# mapleCUx_large_047.net
KiCad netlist of a schematic drawn in EAGLE
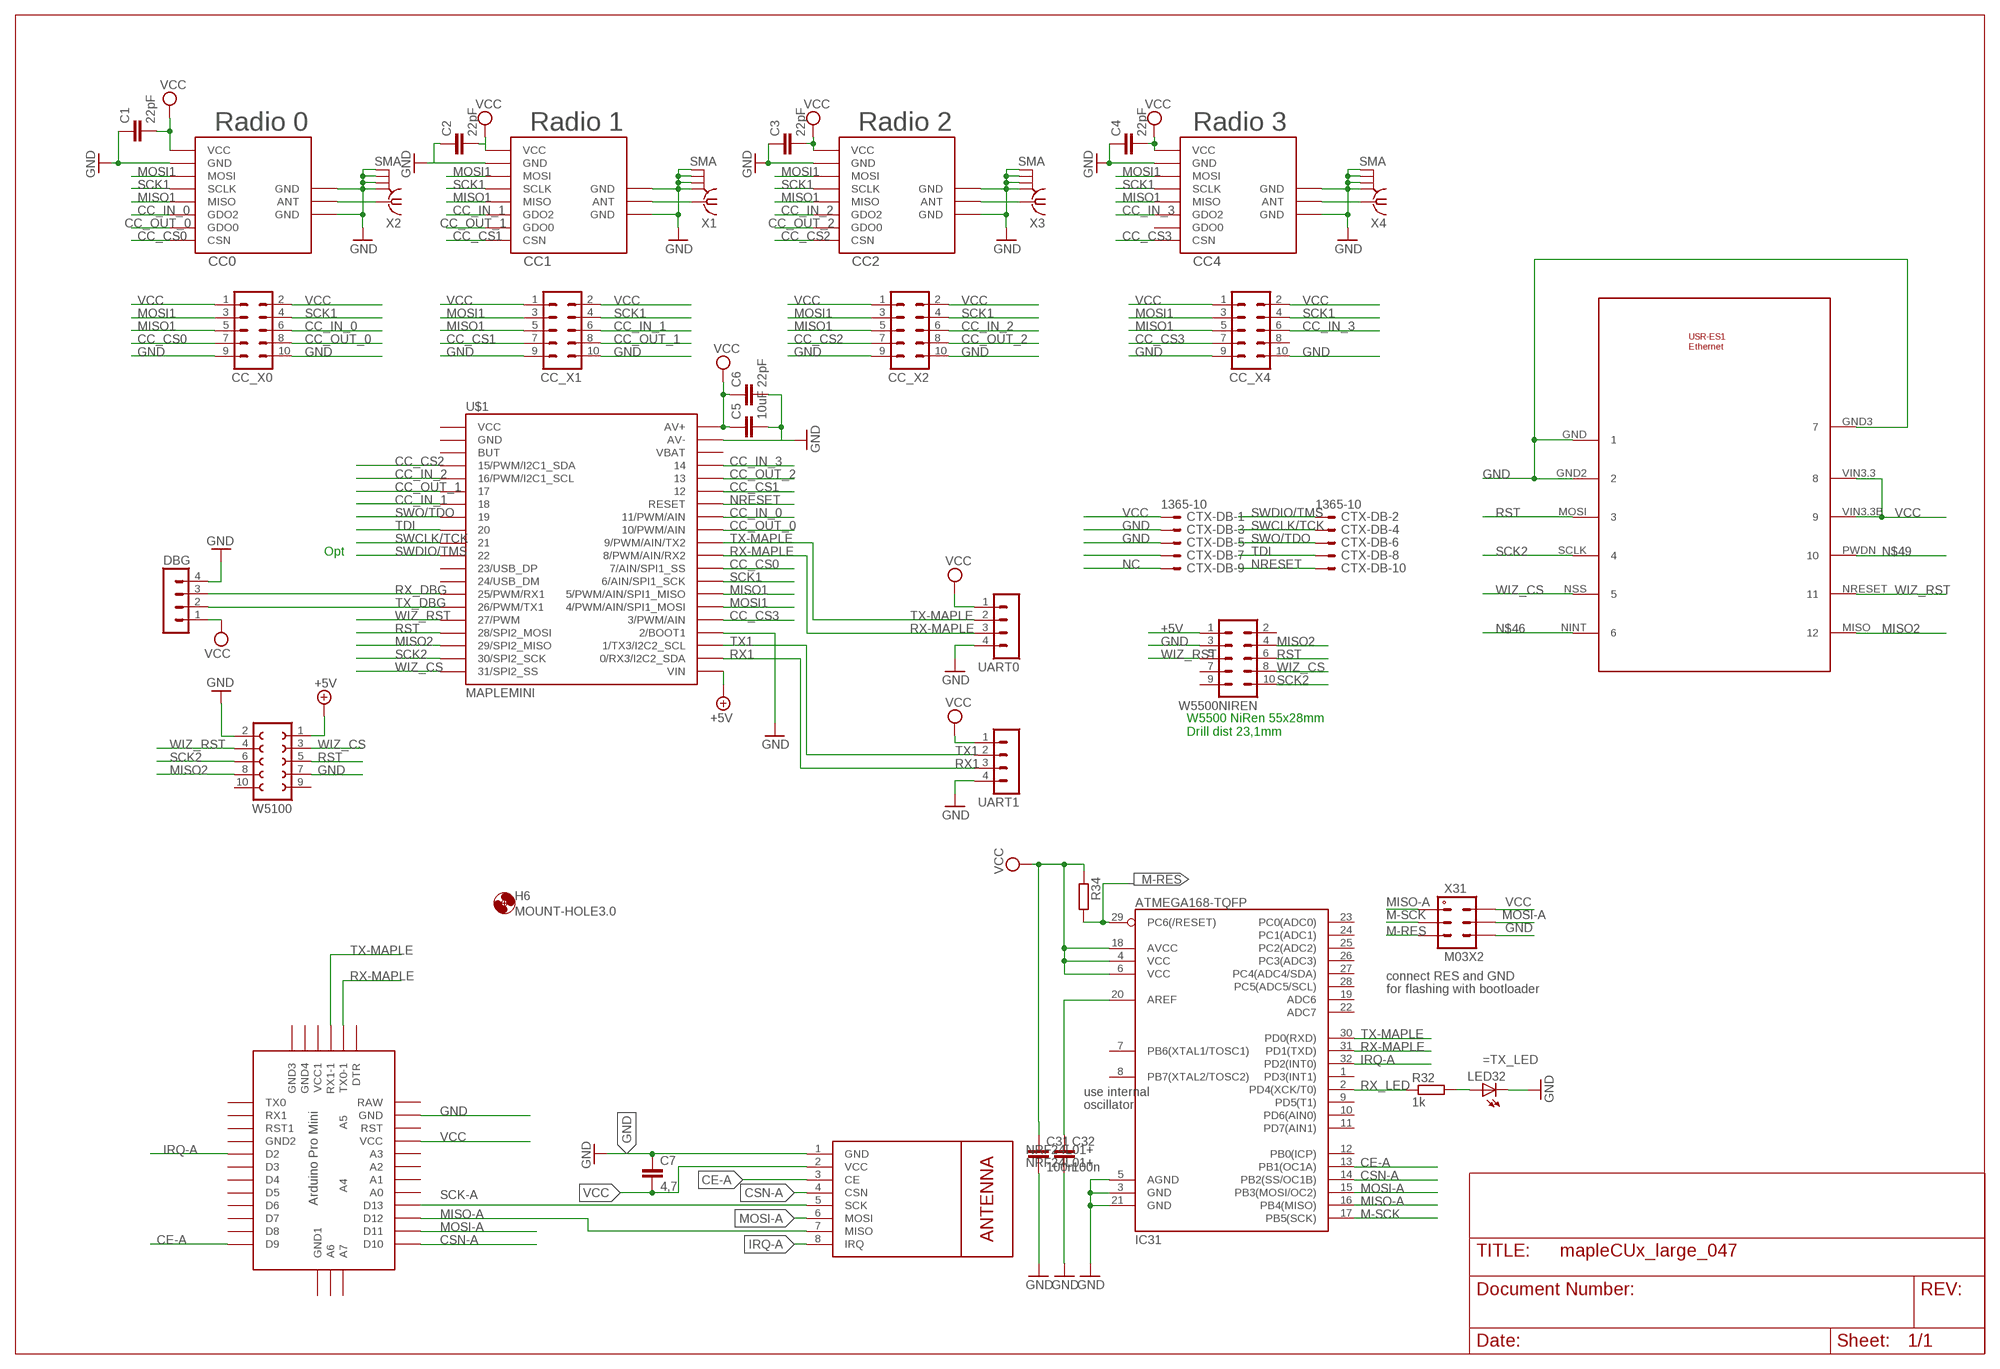
[diagram p0: schematic, sheet 1]

(export (version "E")
  (design (tool "Eeschema 10.0.6"))
  (components
    (comp (ref "C1")
      (value "22pF")
      (footprint "eagle-import:C0805")
      (libsource (lib "eagle-import") (part "C-EUC0805"))
    )
    (comp (ref "C2")
      (value "22pF")
      (footprint "eagle-import:C0805")
      (libsource (lib "eagle-import") (part "C-EUC0805"))
    )
    (comp (ref "C3")
      (value "22pF")
      (footprint "eagle-import:C0805")
      (libsource (lib "eagle-import") (part "C-EUC0805"))
    )
    (comp (ref "C4")
      (value "22pF")
      (footprint "eagle-import:C0805")
      (libsource (lib "eagle-import") (part "C-EUC0805"))
    )
    (comp (ref "C5")
      (value "10uF")
      (footprint "eagle-import:C1210")
      (libsource (lib "eagle-import") (part "C-EUC1210"))
    )
    (comp (ref "C6")
      (value "22pF")
      (footprint "eagle-import:C0805")
      (libsource (lib "eagle-import") (part "C-EUC0805"))
    )
    (comp (ref "C7")
      (value "4,7")
      (footprint "eagle-import:C1210")
      (libsource (lib "eagle-import") (part "C-EUC1210"))
    )
    (comp (ref "C31")
      (value "100n")
      (footprint "eagle-import:C0805")
      (libsource (lib "eagle-import") (part "C-EUC0805"))
    )
    (comp (ref "C32")
      (value "100n")
      (footprint "eagle-import:C0805")
      (libsource (lib "eagle-import") (part "C-EUC0805"))
    )
    (comp (ref "CC0")
      (value "CC1101_MODULE1SMD")
      (footprint "eagle-import:CC1101_MODULE1_SMD")
      (libsource (lib "eagle-import") (part "CC1101_MODULE1SMD"))
    )
    (comp (ref "CC1")
      (value "CC1101_MODULE1SMD")
      (footprint "eagle-import:CC1101_MODULE1_SMD")
      (libsource (lib "eagle-import") (part "CC1101_MODULE1SMD"))
    )
    (comp (ref "CC2")
      (value "CC1101_MODULE1SMD")
      (footprint "eagle-import:CC1101_MODULE1_SMD")
      (libsource (lib "eagle-import") (part "CC1101_MODULE1SMD"))
    )
    (comp (ref "CC4")
      (value "CC1101_MODULE1SMD")
      (footprint "eagle-import:CC1101_MODULE1_SMD")
      (libsource (lib "eagle-import") (part "CC1101_MODULE1SMD"))
    )
    (comp (ref "CC_X0")
      (value "MA05-2")
      (footprint "eagle-import:MA05-2")
      (libsource (lib "eagle-import") (part "MA05-2"))
    )
    (comp (ref "CC_X1")
      (value "MA05-2")
      (footprint "eagle-import:MA05-2")
      (libsource (lib "eagle-import") (part "MA05-2"))
    )
    (comp (ref "CC_X2")
      (value "MA05-2")
      (footprint "eagle-import:MA05-2")
      (libsource (lib "eagle-import") (part "MA05-2"))
    )
    (comp (ref "CC_X4")
      (value "MA05-2")
      (footprint "eagle-import:MA05-2")
      (libsource (lib "eagle-import") (part "MA05-2"))
    )
    (comp (ref "CTX-DB")
      (value "1365-10")
      (footprint "eagle-import:1365-10")
      (libsource (lib "eagle-import") (part "1365-10"))
    )
    (comp (ref "DBG")
      (value "MA04-1")
      (footprint "eagle-import:MA04-1")
      (libsource (lib "eagle-import") (part "MA04-1"))
    )
    (comp (ref "H6")
      (value "MOUNT-HOLE3.0")
      (footprint "eagle-import:3,0")
      (libsource (lib "eagle-import") (part "MOUNT-HOLE3.0"))
    )
    (comp (ref "IC31")
      (value "ATMEGA168-TQFP")
      (footprint "eagle-import:TQFP32-08")
      (libsource (lib "eagle-import") (part "ATMEGA168-TQFP"))
    )
    (comp (ref "LED32")
      (value "LEDCHIPLED_0805")
      (footprint "eagle-import:CHIPLED_0805")
      (libsource (lib "eagle-import") (part "LEDCHIPLED_0805"))
    )
    (comp (ref "NRF24L01+")
      (value "NRF24L01+")
      (footprint "eagle-import:WIRELESS-NRF24L01")
      (libsource (lib "eagle-import") (part "WIRELESS-NRF24L01"))
    )
    (comp (ref "R32")
      (value "1k")
      (footprint "eagle-import:R0805")
      (libsource (lib "eagle-import") (part "R-EU_R0805"))
    )
    (comp (ref "R34")
      (value "R-EU_R0805")
      (footprint "eagle-import:R0805")
      (libsource (lib "eagle-import") (part "R-EU_R0805"))
    )
    (comp (ref "U$1")
      (value "MAPLEMINI")
      (footprint "eagle-import:20-DIP")
      (libsource (lib "eagle-import") (part "MAPLEMINI"))
    )
    (comp (ref "U$2")
      (value "ABK-PRO-MINI")
      (footprint "eagle-import:ABK-PRO-MINI")
      (libsource (lib "eagle-import") (part "ABK-PRO-MINI"))
    )
    (comp (ref "U$3")
      (value "USR-ES1")
      (footprint "eagle-import:USR-ES1")
      (libsource (lib "eagle-import") (part "USR-ES1"))
    )
    (comp (ref "UART0")
      (value "MA04-1")
      (footprint "eagle-import:MA04-1")
      (libsource (lib "eagle-import") (part "MA04-1"))
    )
    (comp (ref "UART1")
      (value "MA04-1")
      (footprint "eagle-import:MA04-1")
      (libsource (lib "eagle-import") (part "MA04-1"))
    )
    (comp (ref "W5100")
      (value "FE05-2")
      (footprint "eagle-import:FE05-2")
      (libsource (lib "eagle-import") (part "FE05-2"))
    )
    (comp (ref "W5500NIREN")
      (value "MA05-2")
      (footprint "eagle-import:MA05-2")
      (libsource (lib "eagle-import") (part "MA05-2"))
    )
    (comp (ref "X1")
      (value "SMA")
      (footprint "eagle-import:SMA")
      (libsource (lib "eagle-import") (part "SMA"))
    )
    (comp (ref "X2")
      (value "SMA")
      (footprint "eagle-import:SMA")
      (libsource (lib "eagle-import") (part "SMA"))
    )
    (comp (ref "X3")
      (value "SMA")
      (footprint "eagle-import:SMA")
      (libsource (lib "eagle-import") (part "SMA"))
    )
    (comp (ref "X4")
      (value "SMA")
      (footprint "eagle-import:SMA")
      (libsource (lib "eagle-import") (part "SMA"))
    )
    (comp (ref "X31")
      (value "M03X2")
      (footprint "eagle-import:2X03-1.27MM_SMD")
      (libsource (lib "eagle-import") (part "M03X2"))
    )
  )
  (nets
    (net (code "1") (name "+5V") (class "Default")
      (node (ref "U$1") (pin "21") (pinfunction "VIN_21") (pintype "bidirectional"))
      (node (ref "W5100") (pin "1") (pinfunction "1_1") (pintype "passive"))
      (node (ref "W5500NIREN") (pin "1") (pinfunction "1_1") (pintype "passive"))
    )
    (net (code "2") (name "/CC_CS0") (class "Default")
      (node (ref "CC0") (pin "CSN") (pinfunction "CSN_CSN") (pintype "bidirectional"))
      (node (ref "CC_X0") (pin "7") (pinfunction "7_7") (pintype "passive"))
      (node (ref "U$1") (pin "29") (pinfunction "7/AIN/SPI1_SS_29") (pintype "bidirectional"))
    )
    (net (code "3") (name "/CC_CS1") (class "Default")
      (node (ref "CC1") (pin "CSN") (pinfunction "CSN_CSN") (pintype "bidirectional"))
      (node (ref "CC_X1") (pin "7") (pinfunction "7_7") (pintype "passive"))
      (node (ref "U$1") (pin "35") (pinfunction "12_35") (pintype "bidirectional"))
    )
    (net (code "4") (name "/CC_CS2") (class "Default")
      (node (ref "CC2") (pin "CSN") (pinfunction "CSN_CSN") (pintype "bidirectional"))
      (node (ref "CC_X2") (pin "7") (pinfunction "7_7") (pintype "passive"))
      (node (ref "U$1") (pin "4") (pinfunction "15/PWM/I2C1_SDA_4") (pintype "bidirectional"))
    )
    (net (code "5") (name "/CC_CS3") (class "Default")
      (node (ref "CC4") (pin "CSN") (pinfunction "CSN_CSN") (pintype "bidirectional"))
      (node (ref "CC_X4") (pin "7") (pinfunction "7_7") (pintype "passive"))
      (node (ref "U$1") (pin "25") (pinfunction "3/PWM/AIN_25") (pintype "bidirectional"))
    )
    (net (code "6") (name "/CC_IN_0") (class "Default")
      (node (ref "CC0") (pin "GDO2") (pinfunction "GDO2_GDO2") (pintype "bidirectional"))
      (node (ref "CC_X0") (pin "6") (pinfunction "6_6") (pintype "passive"))
      (node (ref "U$1") (pin "33") (pinfunction "11/PWM/AIN_33") (pintype "bidirectional"))
    )
    (net (code "7") (name "/CC_IN_1") (class "Default")
      (node (ref "CC1") (pin "GDO2") (pinfunction "GDO2_GDO2") (pintype "bidirectional"))
      (node (ref "CC_X1") (pin "6") (pinfunction "6_6") (pintype "passive"))
      (node (ref "U$1") (pin "7") (pinfunction "18_7") (pintype "bidirectional"))
    )
    (net (code "8") (name "/CC_IN_2") (class "Default")
      (node (ref "CC2") (pin "GDO2") (pinfunction "GDO2_GDO2") (pintype "bidirectional"))
      (node (ref "CC_X2") (pin "6") (pinfunction "6_6") (pintype "passive"))
      (node (ref "U$1") (pin "5") (pinfunction "16/PWM/I2C1_SCL_5") (pintype "bidirectional"))
    )
    (net (code "9") (name "/CC_IN_3") (class "Default")
      (node (ref "CC4") (pin "GDO2") (pinfunction "GDO2_GDO2") (pintype "bidirectional"))
      (node (ref "CC_X4") (pin "6") (pinfunction "6_6") (pintype "passive"))
      (node (ref "U$1") (pin "37") (pinfunction "14_37") (pintype "bidirectional"))
    )
    (net (code "10") (name "/CC_OUT_0") (class "Default")
      (node (ref "CC0") (pin "GDO0") (pinfunction "GDO0_GDO0") (pintype "bidirectional"))
      (node (ref "CC_X0") (pin "8") (pinfunction "8_8") (pintype "passive"))
      (node (ref "U$1") (pin "32") (pinfunction "10/PWM/AIN_32") (pintype "bidirectional"))
    )
    (net (code "11") (name "/CC_OUT_1") (class "Default")
      (node (ref "CC1") (pin "GDO0") (pinfunction "GDO0_GDO0") (pintype "bidirectional"))
      (node (ref "CC_X1") (pin "8") (pinfunction "8_8") (pintype "passive"))
      (node (ref "U$1") (pin "6") (pinfunction "17_6") (pintype "bidirectional"))
    )
    (net (code "12") (name "/CC_OUT_2") (class "Default")
      (node (ref "CC2") (pin "GDO0") (pinfunction "GDO0_GDO0") (pintype "bidirectional"))
      (node (ref "CC_X2") (pin "8") (pinfunction "8_8") (pintype "passive"))
      (node (ref "U$1") (pin "36") (pinfunction "13_36") (pintype "bidirectional"))
    )
    (net (code "13") (name "/M-RES") (class "Default")
      (node (ref "IC31") (pin "29") (pinfunction "PC6(/RESET)_29") (pintype "bidirectional"))
      (node (ref "R34") (pin "2") (pinfunction "2_2") (pintype "passive"))
      (node (ref "X31") (pin "P$5") (pinfunction "5_P$5") (pintype "passive"))
    )
    (net (code "14") (name "/M-SCK") (class "Default")
      (node (ref "IC31") (pin "17") (pinfunction "PB5(SCK)_17") (pintype "bidirectional"))
      (node (ref "X31") (pin "P$3") (pinfunction "3_P$3") (pintype "passive"))
    )
    (net (code "15") (name "/MISO-A") (class "Default")
      (node (ref "IC31") (pin "16") (pinfunction "PB4(MISO)_16") (pintype "bidirectional"))
      (node (ref "NRF24L01+") (pin "7") (pinfunction "MISO_7") (pintype "bidirectional"))
      (node (ref "U$2") (pin "D12") (pinfunction "D12_D12") (pintype "bidirectional"))
      (node (ref "X31") (pin "P$1") (pinfunction "1_P$1") (pintype "passive"))
    )
    (net (code "16") (name "/MISO1") (class "Default")
      (node (ref "CC0") (pin "MISO") (pinfunction "MISO_MISO") (pintype "bidirectional"))
      (node (ref "CC1") (pin "MISO") (pinfunction "MISO_MISO") (pintype "bidirectional"))
      (node (ref "CC2") (pin "MISO") (pinfunction "MISO_MISO") (pintype "bidirectional"))
      (node (ref "CC4") (pin "MISO") (pinfunction "MISO_MISO") (pintype "bidirectional"))
      (node (ref "CC_X0") (pin "5") (pinfunction "5_5") (pintype "passive"))
      (node (ref "CC_X1") (pin "5") (pinfunction "5_5") (pintype "passive"))
      (node (ref "CC_X2") (pin "5") (pinfunction "5_5") (pintype "passive"))
      (node (ref "CC_X4") (pin "5") (pinfunction "5_5") (pintype "passive"))
      (node (ref "U$1") (pin "27") (pinfunction "5/PWM/AIN/SPI1_MISO_27") (pintype "bidirectional"))
    )
    (net (code "17") (name "/MISO2") (class "Default")
      (node (ref "U$1") (pin "18") (pinfunction "29/SPI2_MISO_18") (pintype "bidirectional"))
      (node (ref "U$3") (pin "MISO") (pinfunction "12_MISO") (pintype "bidirectional"))
      (node (ref "W5100") (pin "8") (pinfunction "8_8") (pintype "passive"))
      (node (ref "W5500NIREN") (pin "4") (pinfunction "4_4") (pintype "passive"))
    )
    (net (code "18") (name "/MOSI1") (class "Default")
      (node (ref "CC0") (pin "MOSI") (pinfunction "MOSI_MOSI") (pintype "bidirectional"))
      (node (ref "CC1") (pin "MOSI") (pinfunction "MOSI_MOSI") (pintype "bidirectional"))
      (node (ref "CC2") (pin "MOSI") (pinfunction "MOSI_MOSI") (pintype "bidirectional"))
      (node (ref "CC4") (pin "MOSI") (pinfunction "MOSI_MOSI") (pintype "bidirectional"))
      (node (ref "CC_X0") (pin "3") (pinfunction "3_3") (pintype "passive"))
      (node (ref "CC_X1") (pin "3") (pinfunction "3_3") (pintype "passive"))
      (node (ref "CC_X2") (pin "3") (pinfunction "3_3") (pintype "passive"))
      (node (ref "CC_X4") (pin "3") (pinfunction "3_3") (pintype "passive"))
      (node (ref "U$1") (pin "26") (pinfunction "4/PWM/AIN/SPI1_MOSI_26") (pintype "bidirectional"))
    )
    (net (code "19") (name "/N$46") (class "Default")
      (node (ref "U$3") (pin "NINT") (pinfunction "6_NINT") (pintype "bidirectional"))
    )
    (net (code "20") (name "/N$49") (class "Default")
      (node (ref "U$3") (pin "PWDN") (pinfunction "10_PWDN") (pintype "bidirectional"))
    )
    (net (code "21") (name "/NC") (class "Default")
      (node (ref "CTX-DB") (pin "9") (pinfunction "S_9") (pintype "passive"))
    )
    (net (code "22") (name "/NRESET") (class "Default")
      (node (ref "CTX-DB") (pin "10") (pinfunction "S_10") (pintype "passive"))
      (node (ref "U$1") (pin "34") (pinfunction "RESET_34") (pintype "bidirectional"))
    )
    (net (code "23") (name "/RST") (class "Default")
      (node (ref "U$1") (pin "17") (pinfunction "28/SPI2_MOSI_17") (pintype "bidirectional"))
      (node (ref "U$3") (pin "MOSI") (pinfunction "3_MOSI") (pintype "bidirectional"))
      (node (ref "W5100") (pin "5") (pinfunction "5_5") (pintype "passive"))
      (node (ref "W5500NIREN") (pin "6") (pinfunction "6_6") (pintype "passive"))
    )
    (net (code "24") (name "/RX-MAPLE") (class "Default")
      (node (ref "IC31") (pin "31") (pinfunction "PD1(TXD)_31") (pintype "bidirectional"))
      (node (ref "U$1") (pin "30") (pinfunction "8/PWM/AIN/RX2_30") (pintype "bidirectional"))
      (node (ref "U$2") (pin "TX0-1") (pinfunction "TX0-1_TX0-1") (pintype "bidirectional"))
      (node (ref "UART0") (pin "3") (pinfunction "3_3") (pintype "passive"))
    )
    (net (code "25") (name "/RX1") (class "Default")
      (node (ref "U$1") (pin "22") (pinfunction "0/RX3/I2C2_SDA_22") (pintype "bidirectional"))
      (node (ref "UART1") (pin "3") (pinfunction "3_3") (pintype "passive"))
    )
    (net (code "26") (name "/RX_DBG") (class "Default")
      (node (ref "DBG") (pin "3") (pinfunction "3_3") (pintype "passive"))
      (node (ref "U$1") (pin "14") (pinfunction "25/PWM/RX1_14") (pintype "bidirectional"))
    )
    (net (code "27") (name "/RX_LED") (class "Default")
      (node (ref "IC31") (pin "2") (pinfunction "PD4(XCK/T0)_2") (pintype "bidirectional"))
      (node (ref "R32") (pin "1") (pinfunction "1_1") (pintype "passive"))
    )
    (net (code "28") (name "/SCK-A") (class "Default")
      (node (ref "NRF24L01+") (pin "5") (pinfunction "SCK_5") (pintype "bidirectional"))
      (node (ref "U$2") (pin "D13") (pinfunction "D13_D13") (pintype "bidirectional"))
    )
    (net (code "29") (name "/SCK1") (class "Default")
      (node (ref "CC0") (pin "SCLK") (pinfunction "SCLK_SCLK") (pintype "bidirectional"))
      (node (ref "CC1") (pin "SCLK") (pinfunction "SCLK_SCLK") (pintype "bidirectional"))
      (node (ref "CC2") (pin "SCLK") (pinfunction "SCLK_SCLK") (pintype "bidirectional"))
      (node (ref "CC4") (pin "SCLK") (pinfunction "SCLK_SCLK") (pintype "bidirectional"))
      (node (ref "CC_X0") (pin "4") (pinfunction "4_4") (pintype "passive"))
      (node (ref "CC_X1") (pin "4") (pinfunction "4_4") (pintype "passive"))
      (node (ref "CC_X2") (pin "4") (pinfunction "4_4") (pintype "passive"))
      (node (ref "CC_X4") (pin "4") (pinfunction "4_4") (pintype "passive"))
      (node (ref "U$1") (pin "28") (pinfunction "6/AIN/SPI1_SCK_28") (pintype "bidirectional"))
    )
    (net (code "30") (name "/SCK2") (class "Default")
      (node (ref "U$1") (pin "19") (pinfunction "30/SPI2_SCK_19") (pintype "bidirectional"))
      (node (ref "U$3") (pin "SCLK") (pinfunction "4_SCLK") (pintype "bidirectional"))
      (node (ref "W5100") (pin "6") (pinfunction "6_6") (pintype "passive"))
      (node (ref "W5500NIREN") (pin "10") (pinfunction "10_10") (pintype "passive"))
    )
    (net (code "31") (name "/SWCLK{slash}TCK") (class "Default")
      (node (ref "CTX-DB") (pin "4") (pinfunction "S_4") (pintype "passive"))
      (node (ref "U$1") (pin "10") (pinfunction "21_10") (pintype "bidirectional"))
    )
    (net (code "32") (name "/SWDIO{slash}TMS") (class "Default")
      (node (ref "CTX-DB") (pin "2") (pinfunction "S_2") (pintype "passive"))
      (node (ref "U$1") (pin "11") (pinfunction "22_11") (pintype "bidirectional"))
    )
    (net (code "33") (name "/SWO{slash}TDO") (class "Default")
      (node (ref "CTX-DB") (pin "6") (pinfunction "S_6") (pintype "passive"))
      (node (ref "U$1") (pin "8") (pinfunction "19_8") (pintype "bidirectional"))
    )
    (net (code "34") (name "/TDI") (class "Default")
      (node (ref "CTX-DB") (pin "8") (pinfunction "S_8") (pintype "passive"))
      (node (ref "U$1") (pin "9") (pinfunction "20_9") (pintype "bidirectional"))
    )
    (net (code "35") (name "/TX-MAPLE") (class "Default")
      (node (ref "IC31") (pin "30") (pinfunction "PD0(RXD)_30") (pintype "bidirectional"))
      (node (ref "U$1") (pin "31") (pinfunction "9/PWM/AIN/TX2_31") (pintype "bidirectional"))
      (node (ref "U$2") (pin "RX1-1") (pinfunction "RX1-1_RX1-1") (pintype "bidirectional"))
      (node (ref "UART0") (pin "2") (pinfunction "2_2") (pintype "passive"))
    )
    (net (code "36") (name "/TX1") (class "Default")
      (node (ref "U$1") (pin "23") (pinfunction "1/TX3/I2C2_SCL_23") (pintype "bidirectional"))
      (node (ref "UART1") (pin "2") (pinfunction "2_2") (pintype "passive"))
    )
    (net (code "37") (name "/TX_DBG") (class "Default")
      (node (ref "DBG") (pin "2") (pinfunction "2_2") (pintype "passive"))
      (node (ref "U$1") (pin "15") (pinfunction "26/PWM/TX1_15") (pintype "bidirectional"))
    )
    (net (code "38") (name "/WIZ_CS") (class "Default")
      (node (ref "U$1") (pin "20") (pinfunction "31/SPI2_SS_20") (pintype "bidirectional"))
      (node (ref "U$3") (pin "NSS") (pinfunction "5_NSS") (pintype "bidirectional"))
      (node (ref "W5100") (pin "3") (pinfunction "3_3") (pintype "passive"))
      (node (ref "W5500NIREN") (pin "8") (pinfunction "8_8") (pintype "passive"))
    )
    (net (code "39") (name "/WIZ_RST") (class "Default")
      (node (ref "U$1") (pin "16") (pinfunction "27/PWM_16") (pintype "bidirectional"))
      (node (ref "U$3") (pin "NRESET") (pinfunction "11_NRESET") (pintype "bidirectional"))
      (node (ref "W5100") (pin "4") (pinfunction "4_4") (pintype "passive"))
      (node (ref "W5500NIREN") (pin "5") (pinfunction "5_5") (pintype "passive"))
    )
    (net (code "40") (name "CE-A") (class "Default")
      (node (ref "IC31") (pin "13") (pinfunction "PB1(OC1A)_13") (pintype "bidirectional"))
      (node (ref "NRF24L01+") (pin "3") (pinfunction "CE_3") (pintype "bidirectional"))
      (node (ref "U$2") (pin "D9") (pinfunction "D9_D9") (pintype "bidirectional"))
    )
    (net (code "41") (name "CSN-A") (class "Default")
      (node (ref "IC31") (pin "14") (pinfunction "PB2(SS/OC1B)_14") (pintype "bidirectional"))
      (node (ref "NRF24L01+") (pin "4") (pinfunction "CSN_4") (pintype "bidirectional"))
      (node (ref "U$2") (pin "D10") (pinfunction "D10_D10") (pintype "bidirectional"))
    )
    (net (code "42") (name "GND") (class "Default")
      (node (ref "C1") (pin "1") (pinfunction "1_1") (pintype "passive"))
      (node (ref "C2") (pin "1") (pinfunction "1_1") (pintype "passive"))
      (node (ref "C3") (pin "1") (pinfunction "1_1") (pintype "passive"))
      (node (ref "C31") (pin "2") (pinfunction "2_2") (pintype "passive"))
      (node (ref "C32") (pin "2") (pinfunction "2_2") (pintype "passive"))
      (node (ref "C4") (pin "1") (pinfunction "1_1") (pintype "passive"))
      (node (ref "C5") (pin "2") (pinfunction "2_2") (pintype "passive"))
      (node (ref "C6") (pin "2") (pinfunction "2_2") (pintype "passive"))
      (node (ref "C7") (pin "1") (pinfunction "1_1") (pintype "passive"))
      (node (ref "CC0") (pin "GND@0") (pinfunction "GND_GND@0") (pintype "power_in"))
      (node (ref "CC0") (pin "GND@1") (pinfunction "GND_GND@1") (pintype "power_in"))
      (node (ref "CC0") (pin "GND@2") (pinfunction "GND_GND@2") (pintype "power_in"))
      (node (ref "CC1") (pin "GND@0") (pinfunction "GND_GND@0") (pintype "power_in"))
      (node (ref "CC1") (pin "GND@1") (pinfunction "GND_GND@1") (pintype "power_in"))
      (node (ref "CC1") (pin "GND@2") (pinfunction "GND_GND@2") (pintype "power_in"))
      (node (ref "CC2") (pin "GND@0") (pinfunction "GND_GND@0") (pintype "power_in"))
      (node (ref "CC2") (pin "GND@1") (pinfunction "GND_GND@1") (pintype "power_in"))
      (node (ref "CC2") (pin "GND@2") (pinfunction "GND_GND@2") (pintype "power_in"))
      (node (ref "CC4") (pin "GND@0") (pinfunction "GND_GND@0") (pintype "power_in"))
      (node (ref "CC4") (pin "GND@1") (pinfunction "GND_GND@1") (pintype "power_in"))
      (node (ref "CC4") (pin "GND@2") (pinfunction "GND_GND@2") (pintype "power_in"))
      (node (ref "CC_X0") (pin "10") (pinfunction "10_10") (pintype "passive"))
      (node (ref "CC_X0") (pin "9") (pinfunction "9_9") (pintype "passive"))
      (node (ref "CC_X1") (pin "10") (pinfunction "10_10") (pintype "passive"))
      (node (ref "CC_X1") (pin "9") (pinfunction "9_9") (pintype "passive"))
      (node (ref "CC_X2") (pin "10") (pinfunction "10_10") (pintype "passive"))
      (node (ref "CC_X2") (pin "9") (pinfunction "9_9") (pintype "passive"))
      (node (ref "CC_X4") (pin "10") (pinfunction "10_10") (pintype "passive"))
      (node (ref "CC_X4") (pin "9") (pinfunction "9_9") (pintype "passive"))
      (node (ref "CTX-DB") (pin "3") (pinfunction "S_3") (pintype "passive"))
      (node (ref "CTX-DB") (pin "5") (pinfunction "S_5") (pintype "passive"))
      (node (ref "DBG") (pin "4") (pinfunction "4_4") (pintype "passive"))
      (node (ref "IC31") (pin "21") (pinfunction "GND_21") (pintype "bidirectional"))
      (node (ref "IC31") (pin "3") (pinfunction "GND_3") (pintype "bidirectional"))
      (node (ref "IC31") (pin "5") (pinfunction "AGND_5") (pintype "bidirectional"))
      (node (ref "LED32") (pin "C") (pinfunction "C_C") (pintype "passive"))
      (node (ref "NRF24L01+") (pin "1") (pinfunction "GND_1") (pintype "power_in"))
      (node (ref "U$1") (pin "24") (pinfunction "2/BOOT1_24") (pintype "bidirectional"))
      (node (ref "U$1") (pin "39") (pinfunction "AV-_39") (pintype "bidirectional"))
      (node (ref "U$2") (pin "GND") (pinfunction "GND_GND") (pintype "bidirectional"))
      (node (ref "U$3") (pin "GND") (pinfunction "1_GND") (pintype "power_in"))
      (node (ref "U$3") (pin "GND2") (pinfunction "2_GND2") (pintype "power_in"))
      (node (ref "U$3") (pin "GND3") (pinfunction "7_GND3") (pintype "power_in"))
      (node (ref "UART0") (pin "4") (pinfunction "4_4") (pintype "passive"))
      (node (ref "UART1") (pin "4") (pinfunction "4_4") (pintype "passive"))
      (node (ref "W5100") (pin "2") (pinfunction "2_2") (pintype "passive"))
      (node (ref "W5100") (pin "7") (pinfunction "7_7") (pintype "passive"))
      (node (ref "W5500NIREN") (pin "3") (pinfunction "3_3") (pintype "passive"))
      (node (ref "X1") (pin "GND@1") (pinfunction "2_GND@1") (pintype "passive"))
      (node (ref "X1") (pin "GND@2") (pinfunction "3_GND@2") (pintype "passive"))
      (node (ref "X1") (pin "GND@3") (pinfunction "4_GND@3") (pintype "passive"))
      (node (ref "X1") (pin "GND@4") (pinfunction "5_GND@4") (pintype "passive"))
      (node (ref "X2") (pin "GND@1") (pinfunction "2_GND@1") (pintype "passive"))
      (node (ref "X2") (pin "GND@2") (pinfunction "3_GND@2") (pintype "passive"))
      (node (ref "X2") (pin "GND@3") (pinfunction "4_GND@3") (pintype "passive"))
      (node (ref "X2") (pin "GND@4") (pinfunction "5_GND@4") (pintype "passive"))
      (node (ref "X3") (pin "GND@1") (pinfunction "2_GND@1") (pintype "passive"))
      (node (ref "X3") (pin "GND@2") (pinfunction "3_GND@2") (pintype "passive"))
      (node (ref "X3") (pin "GND@3") (pinfunction "4_GND@3") (pintype "passive"))
      (node (ref "X3") (pin "GND@4") (pinfunction "5_GND@4") (pintype "passive"))
      (node (ref "X31") (pin "P$6") (pinfunction "6_P$6") (pintype "passive"))
      (node (ref "X4") (pin "GND@1") (pinfunction "2_GND@1") (pintype "passive"))
      (node (ref "X4") (pin "GND@2") (pinfunction "3_GND@2") (pintype "passive"))
      (node (ref "X4") (pin "GND@3") (pinfunction "4_GND@3") (pintype "passive"))
      (node (ref "X4") (pin "GND@4") (pinfunction "5_GND@4") (pintype "passive"))
    )
    (net (code "43") (name "IRQ-A") (class "Default")
      (node (ref "IC31") (pin "32") (pinfunction "PD2(INT0)_32") (pintype "bidirectional"))
      (node (ref "NRF24L01+") (pin "8") (pinfunction "IRQ_8") (pintype "bidirectional"))
      (node (ref "U$2") (pin "D2") (pinfunction "D2_D2") (pintype "bidirectional"))
    )
    (net (code "44") (name "MOSI-A") (class "Default")
      (node (ref "IC31") (pin "15") (pinfunction "PB3(MOSI/OC2)_15") (pintype "bidirectional"))
      (node (ref "NRF24L01+") (pin "6") (pinfunction "MOSI_6") (pintype "bidirectional"))
      (node (ref "U$2") (pin "D11") (pinfunction "D11_D11") (pintype "bidirectional"))
      (node (ref "X31") (pin "P$4") (pinfunction "4_P$4") (pintype "passive"))
    )
    (net (code "45") (name "Net-(CC0-PadANT)") (class "Default")
      (node (ref "CC0") (pin "ANT") (pinfunction "ANT_ANT") (pintype "output"))
      (node (ref "X2") (pin "1") (pinfunction "1_1") (pintype "passive"))
    )
    (net (code "46") (name "Net-(CC1-PadANT)") (class "Default")
      (node (ref "CC1") (pin "ANT") (pinfunction "ANT_ANT") (pintype "output"))
      (node (ref "X1") (pin "1") (pinfunction "1_1") (pintype "passive"))
    )
    (net (code "47") (name "Net-(CC2-PadANT)") (class "Default")
      (node (ref "CC2") (pin "ANT") (pinfunction "ANT_ANT") (pintype "output"))
      (node (ref "X3") (pin "1") (pinfunction "1_1") (pintype "passive"))
    )
    (net (code "48") (name "Net-(CC4-PadANT)") (class "Default")
      (node (ref "CC4") (pin "ANT") (pinfunction "ANT_ANT") (pintype "output"))
      (node (ref "X4") (pin "1") (pinfunction "1_1") (pintype "passive"))
    )
    (net (code "49") (name "Net-(IC31-AREF)") (class "Default")
      (node (ref "C32") (pin "1") (pinfunction "1_1") (pintype "passive"))
      (node (ref "IC31") (pin "20") (pinfunction "AREF_20") (pintype "bidirectional"))
    )
    (net (code "50") (name "Net-(LED32-PadA)") (class "Default")
      (node (ref "LED32") (pin "A") (pinfunction "A_A") (pintype "passive"))
      (node (ref "R32") (pin "2") (pinfunction "2_2") (pintype "passive"))
    )
    (net (code "51") (name "VCC") (class "Default")
      (node (ref "C1") (pin "2") (pinfunction "2_2") (pintype "passive"))
      (node (ref "C2") (pin "2") (pinfunction "2_2") (pintype "passive"))
      (node (ref "C3") (pin "2") (pinfunction "2_2") (pintype "passive"))
      (node (ref "C31") (pin "1") (pinfunction "1_1") (pintype "passive"))
      (node (ref "C4") (pin "2") (pinfunction "2_2") (pintype "passive"))
      (node (ref "C5") (pin "1") (pinfunction "1_1") (pintype "passive"))
      (node (ref "C6") (pin "1") (pinfunction "1_1") (pintype "passive"))
      (node (ref "C7") (pin "2") (pinfunction "2_2") (pintype "passive"))
      (node (ref "CC0") (pin "VCC") (pinfunction "VCC_VCC") (pintype "power_in"))
      (node (ref "CC1") (pin "VCC") (pinfunction "VCC_VCC") (pintype "power_in"))
      (node (ref "CC2") (pin "VCC") (pinfunction "VCC_VCC") (pintype "power_in"))
      (node (ref "CC4") (pin "VCC") (pinfunction "VCC_VCC") (pintype "power_in"))
      (node (ref "CC_X0") (pin "1") (pinfunction "1_1") (pintype "passive"))
      (node (ref "CC_X0") (pin "2") (pinfunction "2_2") (pintype "passive"))
      (node (ref "CC_X1") (pin "1") (pinfunction "1_1") (pintype "passive"))
      (node (ref "CC_X1") (pin "2") (pinfunction "2_2") (pintype "passive"))
      (node (ref "CC_X2") (pin "1") (pinfunction "1_1") (pintype "passive"))
      (node (ref "CC_X2") (pin "2") (pinfunction "2_2") (pintype "passive"))
      (node (ref "CC_X4") (pin "1") (pinfunction "1_1") (pintype "passive"))
      (node (ref "CC_X4") (pin "2") (pinfunction "2_2") (pintype "passive"))
      (node (ref "CTX-DB") (pin "1") (pinfunction "S_1") (pintype "passive"))
      (node (ref "DBG") (pin "1") (pinfunction "1_1") (pintype "passive"))
      (node (ref "IC31") (pin "18") (pinfunction "AVCC_18") (pintype "bidirectional"))
      (node (ref "IC31") (pin "4") (pinfunction "VCC_4") (pintype "bidirectional"))
      (node (ref "IC31") (pin "6") (pinfunction "VCC_6") (pintype "bidirectional"))
      (node (ref "NRF24L01+") (pin "2") (pinfunction "VCC_2") (pintype "power_in"))
      (node (ref "R34") (pin "1") (pinfunction "1_1") (pintype "passive"))
      (node (ref "U$1") (pin "40") (pinfunction "AV+_40") (pintype "bidirectional"))
      (node (ref "U$2") (pin "VCC") (pinfunction "VCC_VCC") (pintype "bidirectional"))
      (node (ref "U$3") (pin "VIN3.3") (pinfunction "8_VIN3.3") (pintype "power_in"))
      (node (ref "U$3") (pin "VIN3.3B") (pinfunction "9_VIN3.3B") (pintype "bidirectional"))
      (node (ref "UART0") (pin "1") (pinfunction "1_1") (pintype "passive"))
      (node (ref "UART1") (pin "1") (pinfunction "1_1") (pintype "passive"))
      (node (ref "X31") (pin "P$2") (pinfunction "2_P$2") (pintype "passive"))
    )
    (net (code "52") (name "unconnected-(CC4-PadGDO0)") (class "Default")
      (node (ref "CC4") (pin "GDO0") (pinfunction "GDO0_GDO0") (pintype "bidirectional"))
    )
    (net (code "53") (name "unconnected-(CC_X4-Pad8)") (class "Default")
      (node (ref "CC_X4") (pin "8") (pinfunction "8_8") (pintype "passive"))
    )
    (net (code "54") (name "unconnected-(CTX-DBH-S-Pad7)") (class "Default")
      (node (ref "CTX-DB") (pin "7") (pinfunction "S_7") (pintype "passive"))
    )
    (net (code "55") (name "unconnected-(IC31-ADC6-Pad19)") (class "Default")
      (node (ref "IC31") (pin "19") (pinfunction "ADC6_19") (pintype "bidirectional"))
    )
    (net (code "56") (name "unconnected-(IC31-ADC7-Pad22)") (class "Default")
      (node (ref "IC31") (pin "22") (pinfunction "ADC7_22") (pintype "bidirectional"))
    )
    (net (code "57") (name "unconnected-(IC31-PB0(ICP)-Pad12)") (class "Default")
      (node (ref "IC31") (pin "12") (pinfunction "PB0(ICP)_12") (pintype "bidirectional"))
    )
    (net (code "58") (name "unconnected-(IC31-PB6(XTAL1{slash}TOSC1)-Pad7)") (class "Default")
      (node (ref "IC31") (pin "7") (pinfunction "PB6(XTAL1/TOSC1)_7") (pintype "bidirectional"))
    )
    (net (code "59") (name "unconnected-(IC31-PB7(XTAL2{slash}TOSC2)-Pad8)") (class "Default")
      (node (ref "IC31") (pin "8") (pinfunction "PB7(XTAL2/TOSC2)_8") (pintype "bidirectional"))
    )
    (net (code "60") (name "unconnected-(IC31-PC0(ADC0)-Pad23)") (class "Default")
      (node (ref "IC31") (pin "23") (pinfunction "PC0(ADC0)_23") (pintype "bidirectional"))
    )
    (net (code "61") (name "unconnected-(IC31-PC1(ADC1)-Pad24)") (class "Default")
      (node (ref "IC31") (pin "24") (pinfunction "PC1(ADC1)_24") (pintype "bidirectional"))
    )
    (net (code "62") (name "unconnected-(IC31-PC2(ADC2)-Pad25)") (class "Default")
      (node (ref "IC31") (pin "25") (pinfunction "PC2(ADC2)_25") (pintype "bidirectional"))
    )
    (net (code "63") (name "unconnected-(IC31-PC3(ADC3)-Pad26)") (class "Default")
      (node (ref "IC31") (pin "26") (pinfunction "PC3(ADC3)_26") (pintype "bidirectional"))
    )
    (net (code "64") (name "unconnected-(IC31-PC4(ADC4{slash}SDA)-Pad27)") (class "Default")
      (node (ref "IC31") (pin "27") (pinfunction "PC4(ADC4/SDA)_27") (pintype "bidirectional"))
    )
    (net (code "65") (name "unconnected-(IC31-PC5(ADC5{slash}SCL)-Pad28)") (class "Default")
      (node (ref "IC31") (pin "28") (pinfunction "PC5(ADC5/SCL)_28") (pintype "bidirectional"))
    )
    (net (code "66") (name "unconnected-(IC31-PD3(INT1)-Pad1)") (class "Default")
      (node (ref "IC31") (pin "1") (pinfunction "PD3(INT1)_1") (pintype "bidirectional"))
    )
    (net (code "67") (name "unconnected-(IC31-PD5(T1)-Pad9)") (class "Default")
      (node (ref "IC31") (pin "9") (pinfunction "PD5(T1)_9") (pintype "bidirectional"))
    )
    (net (code "68") (name "unconnected-(IC31-PD6(AIN0)-Pad10)") (class "Default")
      (node (ref "IC31") (pin "10") (pinfunction "PD6(AIN0)_10") (pintype "bidirectional"))
    )
    (net (code "69") (name "unconnected-(IC31-PD7(AIN1)-Pad11)") (class "Default")
      (node (ref "IC31") (pin "11") (pinfunction "PD7(AIN1)_11") (pintype "bidirectional"))
    )
    (net (code "70") (name "unconnected-(U$1-23{slash}USB_DP-Pad12)") (class "Default")
      (node (ref "U$1") (pin "12") (pinfunction "23/USB_DP_12") (pintype "bidirectional"))
    )
    (net (code "71") (name "unconnected-(U$1-24{slash}USB_DM-Pad13)") (class "Default")
      (node (ref "U$1") (pin "13") (pinfunction "24/USB_DM_13") (pintype "bidirectional"))
    )
    (net (code "72") (name "unconnected-(U$1-BUT-Pad3)") (class "Default")
      (node (ref "U$1") (pin "3") (pinfunction "BUT_3") (pintype "bidirectional"))
    )
    (net (code "73") (name "unconnected-(U$1-GND-Pad2)") (class "Default")
      (node (ref "U$1") (pin "2") (pinfunction "GND_2") (pintype "bidirectional"))
    )
    (net (code "74") (name "unconnected-(U$1-VBAT-Pad38)") (class "Default")
      (node (ref "U$1") (pin "38") (pinfunction "VBAT_38") (pintype "bidirectional"))
    )
    (net (code "75") (name "unconnected-(U$1-VCC-Pad1)") (class "Default")
      (node (ref "U$1") (pin "1") (pinfunction "VCC_1") (pintype "bidirectional"))
    )
    (net (code "76") (name "unconnected-(U$2-GND1-PadGND4)") (class "Default")
      (node (ref "U$2") (pin "GND4") (pinfunction "GND1_GND4") (pintype "bidirectional"))
    )
    (net (code "77") (name "unconnected-(U$2-GND2-PadGND1)") (class "Default")
      (node (ref "U$2") (pin "GND1") (pinfunction "GND2_GND1") (pintype "bidirectional"))
    )
    (net (code "78") (name "unconnected-(U$2-GND3-PadGND2)") (class "Default")
      (node (ref "U$2") (pin "GND2") (pinfunction "GND3_GND2") (pintype "bidirectional"))
    )
    (net (code "79") (name "unconnected-(U$2-GND4-PadGND3)") (class "Default")
      (node (ref "U$2") (pin "GND3") (pinfunction "GND4_GND3") (pintype "bidirectional"))
    )
    (net (code "80") (name "unconnected-(U$2-PadA0)") (class "Default")
      (node (ref "U$2") (pin "A0") (pinfunction "A0_A0") (pintype "bidirectional"))
    )
    (net (code "81") (name "unconnected-(U$2-PadA1)") (class "Default")
      (node (ref "U$2") (pin "A1") (pinfunction "A1_A1") (pintype "bidirectional"))
    )
    (net (code "82") (name "unconnected-(U$2-PadA2)") (class "Default")
      (node (ref "U$2") (pin "A2") (pinfunction "A2_A2") (pintype "bidirectional"))
    )
    (net (code "83") (name "unconnected-(U$2-PadA3)") (class "Default")
      (node (ref "U$2") (pin "A3") (pinfunction "A3_A3") (pintype "bidirectional"))
    )
    (net (code "84") (name "unconnected-(U$2-PadA4)") (class "Default")
      (node (ref "U$2") (pin "A4") (pinfunction "A4_A4") (pintype "bidirectional"))
    )
    (net (code "85") (name "unconnected-(U$2-PadA5)") (class "Default")
      (node (ref "U$2") (pin "A5") (pinfunction "A5_A5") (pintype "bidirectional"))
    )
    (net (code "86") (name "unconnected-(U$2-PadA6)") (class "Default")
      (node (ref "U$2") (pin "A6") (pinfunction "A6_A6") (pintype "bidirectional"))
    )
    (net (code "87") (name "unconnected-(U$2-PadA7)") (class "Default")
      (node (ref "U$2") (pin "A7") (pinfunction "A7_A7") (pintype "bidirectional"))
    )
    (net (code "88") (name "unconnected-(U$2-PadD3)") (class "Default")
      (node (ref "U$2") (pin "D3") (pinfunction "D3_D3") (pintype "bidirectional"))
    )
    (net (code "89") (name "unconnected-(U$2-PadD4)") (class "Default")
      (node (ref "U$2") (pin "D4") (pinfunction "D4_D4") (pintype "bidirectional"))
    )
    (net (code "90") (name "unconnected-(U$2-PadD5)") (class "Default")
      (node (ref "U$2") (pin "D5") (pinfunction "D5_D5") (pintype "bidirectional"))
    )
    (net (code "91") (name "unconnected-(U$2-PadD6)") (class "Default")
      (node (ref "U$2") (pin "D6") (pinfunction "D6_D6") (pintype "bidirectional"))
    )
    (net (code "92") (name "unconnected-(U$2-PadD7)") (class "Default")
      (node (ref "U$2") (pin "D7") (pinfunction "D7_D7") (pintype "bidirectional"))
    )
    (net (code "93") (name "unconnected-(U$2-PadD8)") (class "Default")
      (node (ref "U$2") (pin "D8") (pinfunction "D8_D8") (pintype "bidirectional"))
    )
    (net (code "94") (name "unconnected-(U$2-PadDTR)") (class "Default")
      (node (ref "U$2") (pin "DTR") (pinfunction "DTR_DTR") (pintype "bidirectional"))
    )
    (net (code "95") (name "unconnected-(U$2-PadRAW)") (class "Default")
      (node (ref "U$2") (pin "RAW") (pinfunction "RAW_RAW") (pintype "bidirectional"))
    )
    (net (code "96") (name "unconnected-(U$2-PadRST)") (class "Default")
      (node (ref "U$2") (pin "RST") (pinfunction "RST_RST") (pintype "bidirectional"))
    )
    (net (code "97") (name "unconnected-(U$2-PadRST1)") (class "Default")
      (node (ref "U$2") (pin "RST1") (pinfunction "RST1_RST1") (pintype "bidirectional"))
    )
    (net (code "98") (name "unconnected-(U$2-PadRX1)") (class "Default")
      (node (ref "U$2") (pin "RX1") (pinfunction "RX1_RX1") (pintype "bidirectional"))
    )
    (net (code "99") (name "unconnected-(U$2-PadTX0)") (class "Default")
      (node (ref "U$2") (pin "TX0") (pinfunction "TX0_TX0") (pintype "bidirectional"))
    )
    (net (code "100") (name "unconnected-(U$2-PadVCC1)") (class "Default")
      (node (ref "U$2") (pin "VCC1") (pinfunction "VCC1_VCC1") (pintype "bidirectional"))
    )
    (net (code "101") (name "unconnected-(W5100-Pad9)") (class "Default")
      (node (ref "W5100") (pin "9") (pinfunction "9_9") (pintype "passive"))
    )
    (net (code "102") (name "unconnected-(W5100-Pad10)") (class "Default")
      (node (ref "W5100") (pin "10") (pinfunction "10_10") (pintype "passive"))
    )
    (net (code "103") (name "unconnected-(W5500NIREN-Pad2)") (class "Default")
      (node (ref "W5500NIREN") (pin "2") (pinfunction "2_2") (pintype "passive"))
    )
    (net (code "104") (name "unconnected-(W5500NIREN-Pad7)") (class "Default")
      (node (ref "W5500NIREN") (pin "7") (pinfunction "7_7") (pintype "passive"))
    )
    (net (code "105") (name "unconnected-(W5500NIREN-Pad9)") (class "Default")
      (node (ref "W5500NIREN") (pin "9") (pinfunction "9_9") (pintype "passive"))
    )
  )
)
